# FDL-3_PWR_-_v2.net
KiCad netlist of a schematic drawn in EAGLE
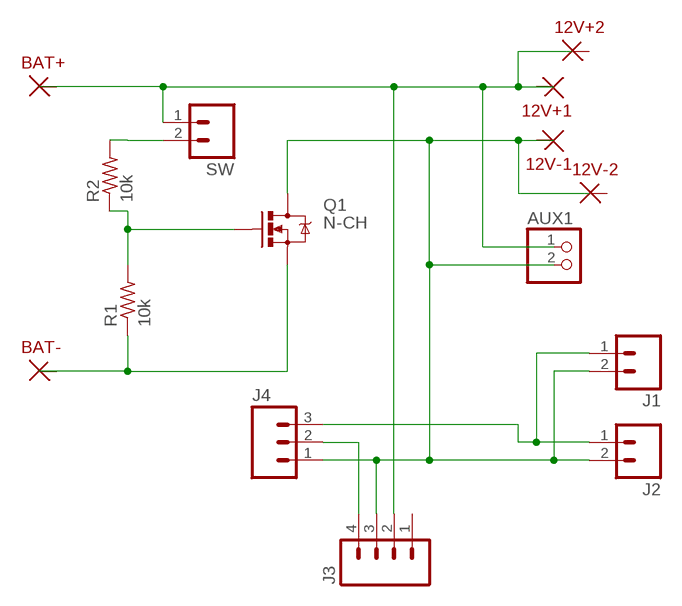
[diagram p0: schematic, sheet 1]

(export (version "E")
  (design (tool "Eeschema 10.0.6"))
  (components
    (comp (ref "12V+1")
      (value "PWRPAD18")
      (footprint "eagle-import:PWRPAD18")
      (libsource (lib "eagle-import") (part "PWRPAD18"))
    )
    (comp (ref "12V+2")
      (value "PWRPAD18")
      (footprint "eagle-import:PWRPAD18")
      (libsource (lib "eagle-import") (part "PWRPAD18"))
    )
    (comp (ref "12V-1")
      (value "PWRPAD18")
      (footprint "eagle-import:PWRPAD18")
      (libsource (lib "eagle-import") (part "PWRPAD18"))
    )
    (comp (ref "12V-2")
      (value "PWRPAD18")
      (footprint "eagle-import:PWRPAD18")
      (libsource (lib "eagle-import") (part "PWRPAD18"))
    )
    (comp (ref "AUX1")
      (value "PINHD-1X2")
      (footprint "eagle-import:1X02")
      (libsource (lib "eagle-import") (part "PINHD-1X2"))
    )
    (comp (ref "BAT+")
      (value "PWRPAD16")
      (footprint "eagle-import:PWRPAD16")
      (libsource (lib "eagle-import") (part "PWRPAD16"))
    )
    (comp (ref "BAT-")
      (value "PWRPAD16")
      (footprint "eagle-import:PWRPAD16")
      (libsource (lib "eagle-import") (part "PWRPAD16"))
    )
    (comp (ref "J1")
      (value "M02PTH")
      (footprint "eagle-import:1X02")
      (libsource (lib "eagle-import") (part "M02PTH"))
    )
    (comp (ref "J2")
      (value "M02PTH")
      (footprint "eagle-import:1X02")
      (libsource (lib "eagle-import") (part "M02PTH"))
    )
    (comp (ref "J3")
      (value "M04PTH")
      (footprint "eagle-import:1X04")
      (libsource (lib "eagle-import") (part "M04PTH"))
    )
    (comp (ref "J4")
      (value "M03PTH")
      (footprint "eagle-import:1X03")
      (libsource (lib "eagle-import") (part "M03PTH"))
    )
    (comp (ref "Q1")
      (value "N-CH")
      (footprint "eagle-import:TO220V")
      (libsource (lib "eagle-import") (part "MOSFET-NCHANNELFQP30N06L"))
    )
    (comp (ref "R1")
      (value "10k")
      (footprint "eagle-import:0204_5")
      (libsource (lib "eagle-import") (part "R-US_0204/5"))
    )
    (comp (ref "R2")
      (value "10k")
      (footprint "eagle-import:0204_5")
      (libsource (lib "eagle-import") (part "R-US_0204/5"))
    )
    (comp (ref "SW")
      (value "M02PTH")
      (footprint "eagle-import:1X02")
      (libsource (lib "eagle-import") (part "M02PTH"))
    )
  )
  (nets
    (net (code "1") (name "Net-(12V+1-PadP$1)") (class "Default")
      (node (ref "12V+1") (pin "P$1") (pinfunction "P$1_P$1") (pintype "bidirectional"))
      (node (ref "12V+2") (pin "P$1") (pinfunction "P$1_P$1") (pintype "bidirectional"))
      (node (ref "AUX1") (pin "1") (pinfunction "1_1") (pintype "passive"))
      (node (ref "BAT+") (pin "P$1") (pinfunction "P$1_P$1") (pintype "bidirectional"))
      (node (ref "J3") (pin "2") (pinfunction "2_2") (pintype "passive"))
      (node (ref "SW") (pin "1") (pinfunction "1_1") (pintype "passive"))
    )
    (net (code "2") (name "Net-(J1-Pad1)") (class "Default")
      (node (ref "J1") (pin "1") (pinfunction "1_1") (pintype "passive"))
      (node (ref "J2") (pin "1") (pinfunction "1_1") (pintype "passive"))
      (node (ref "J4") (pin "3") (pinfunction "3_3") (pintype "passive"))
    )
    (net (code "3") (name "Net-(J3-Pad4)") (class "Default")
      (node (ref "J3") (pin "4") (pinfunction "4_4") (pintype "passive"))
      (node (ref "J4") (pin "2") (pinfunction "2_2") (pintype "passive"))
    )
    (net (code "4") (name "Net-(Q1-D)") (class "Default")
      (node (ref "12V-1") (pin "P$1") (pinfunction "P$1_P$1") (pintype "bidirectional"))
      (node (ref "12V-2") (pin "P$1") (pinfunction "P$1_P$1") (pintype "bidirectional"))
      (node (ref "AUX1") (pin "2") (pinfunction "2_2") (pintype "passive"))
      (node (ref "J1") (pin "2") (pinfunction "2_2") (pintype "passive"))
      (node (ref "J2") (pin "2") (pinfunction "2_2") (pintype "passive"))
      (node (ref "J3") (pin "3") (pinfunction "3_3") (pintype "passive"))
      (node (ref "J4") (pin "1") (pinfunction "1_1") (pintype "passive"))
      (node (ref "Q1") (pin "2") (pinfunction "D_2") (pintype "passive"))
    )
    (net (code "5") (name "Net-(Q1-G)") (class "Default")
      (node (ref "Q1") (pin "1") (pinfunction "G_1") (pintype "passive"))
      (node (ref "R1") (pin "2") (pinfunction "2_2") (pintype "passive"))
      (node (ref "R2") (pin "1") (pinfunction "1_1") (pintype "passive"))
    )
    (net (code "6") (name "Net-(Q1-S)") (class "Default")
      (node (ref "BAT-") (pin "P$1") (pinfunction "P$1_P$1") (pintype "bidirectional"))
      (node (ref "Q1") (pin "3") (pinfunction "S_3") (pintype "passive"))
      (node (ref "R1") (pin "1") (pinfunction "1_1") (pintype "passive"))
    )
    (net (code "7") (name "Net-(R2-Pad2)") (class "Default")
      (node (ref "R2") (pin "2") (pinfunction "2_2") (pintype "passive"))
      (node (ref "SW") (pin "2") (pinfunction "2_2") (pintype "passive"))
    )
    (net (code "8") (name "unconnected-(J3-Pad1)") (class "Default")
      (node (ref "J3") (pin "1") (pinfunction "1_1") (pintype "passive"))
    )
  )
)
